# RAM.net
KiCad netlist of a schematic drawn in Altium Designer
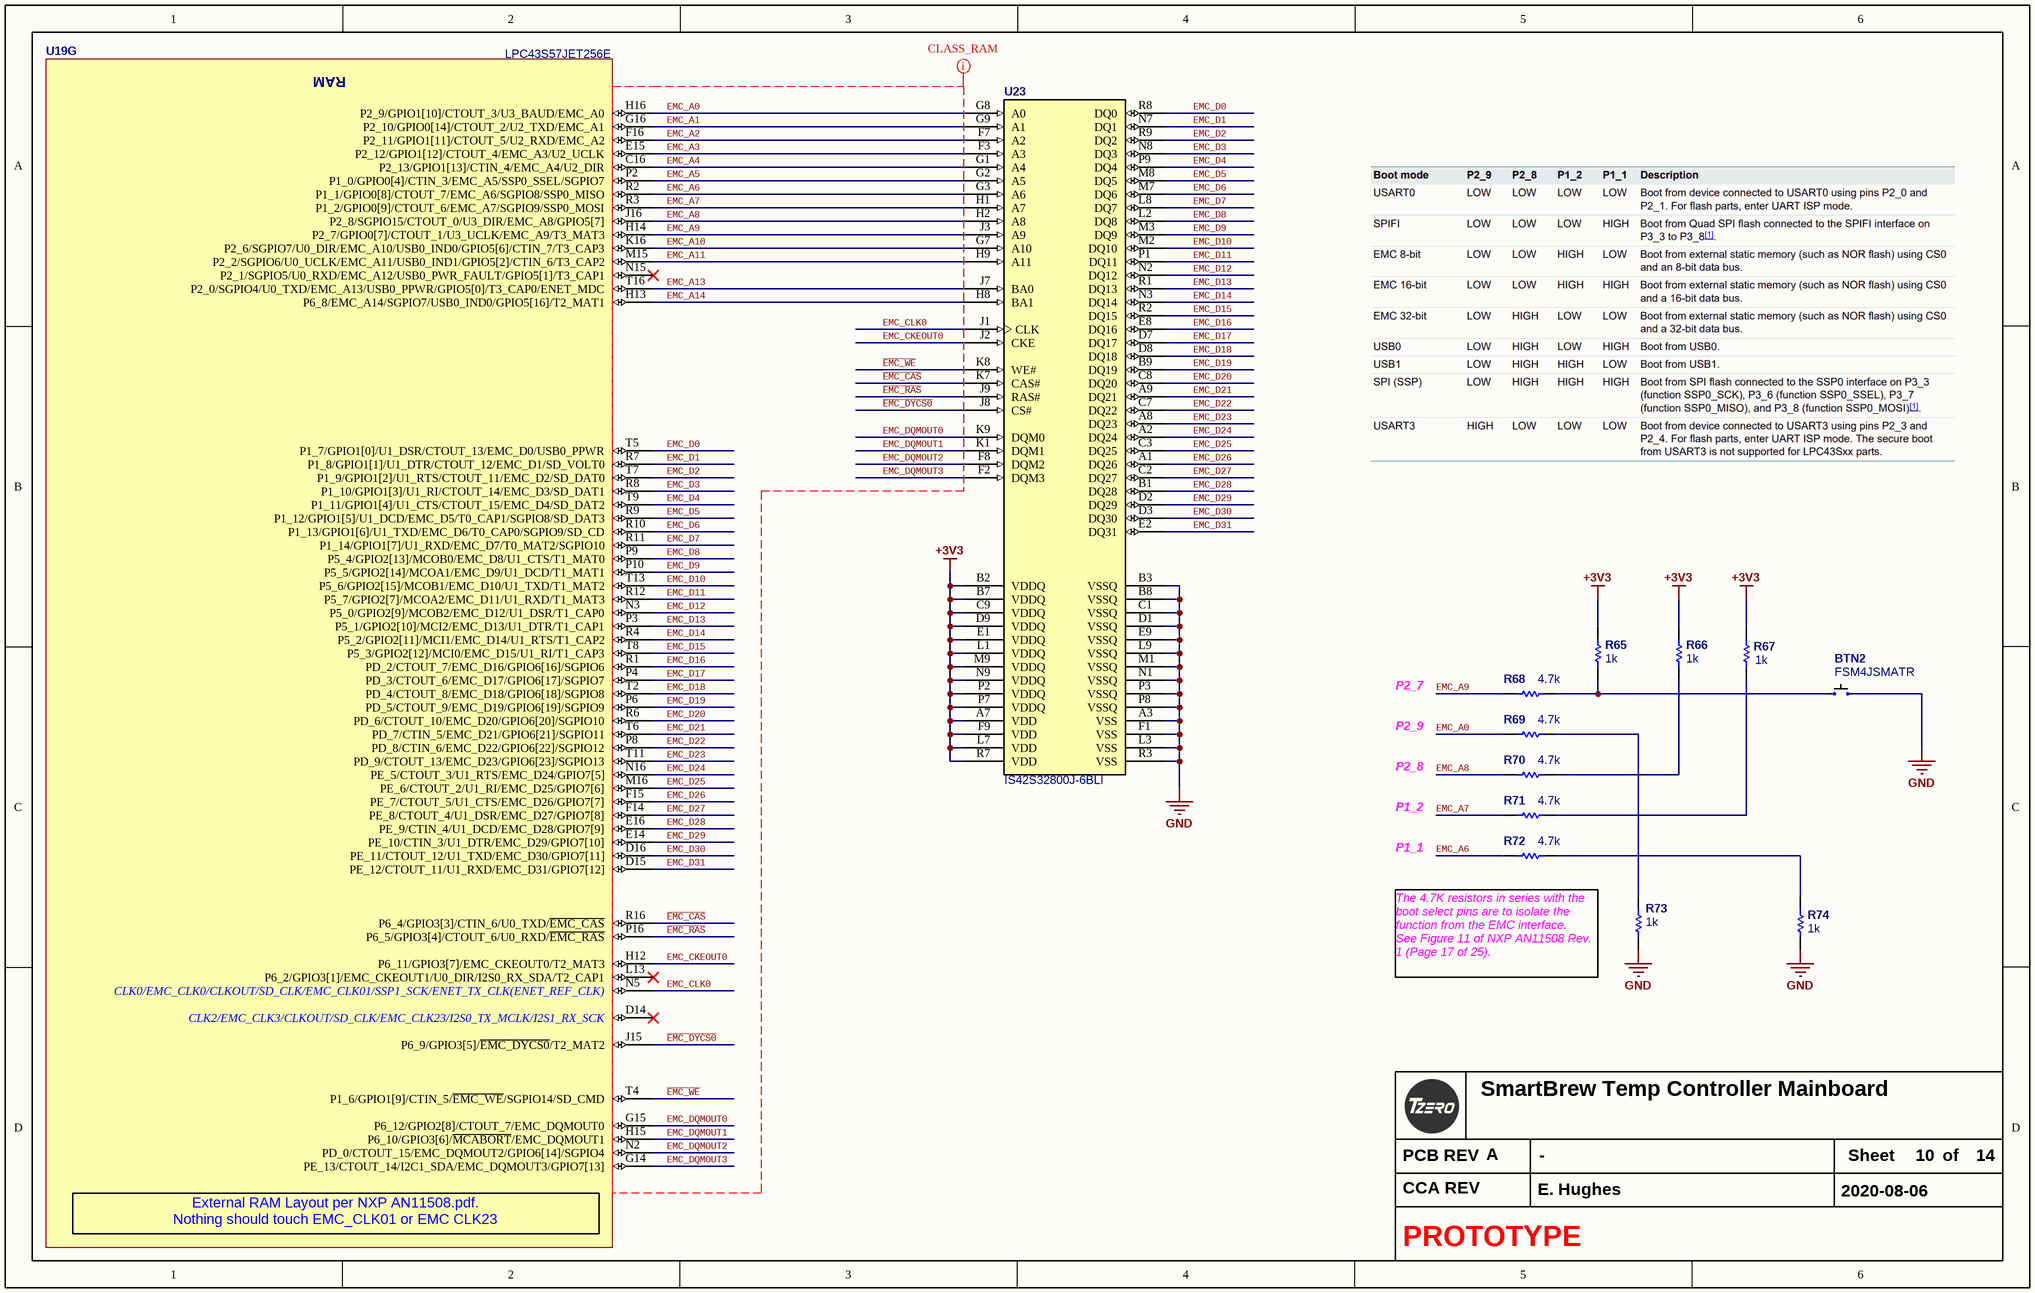
[diagram p0: RAM.SchDoc]

(export (version "E")
  (design (tool "Eeschema 10.0.6"))
  (components
    (comp (ref "BTN2")
      (value "FSM4JSMATR")
      (footprint "FSM4JSMA")
      (description "SWITCH TACTILE SPST-NO 0.05A 12V")
      (fields (field (name "MANUFACTURER") "TE Connectivity"))
      (libsource (lib "eElectroMechanical") (part "FSM4JSMATR"))
    )
    (comp (ref "R65")
      (value "1k")
      (footprint "R0603_0.55MM_MD")
      (description "RES 1K OHM 1/10W 1% 0603 SMD")
      (fields
        (field (name "MANUFACTURER") "Panasonic Electronic Components")
        (field (name "MANUFACTURER PART NUMBER") "ERJ-3EKF1001V")
      )
      (libsource (lib "Resistors - Panasonic - AEC-Q200") (part "R_2P"))
    )
    (comp (ref "R66")
      (value "1k")
      (footprint "R0603_0.55MM_MD")
      (description "RES 1K OHM 1/10W 1% 0603 SMD")
      (fields
        (field (name "MANUFACTURER") "Panasonic Electronic Components")
        (field (name "MANUFACTURER PART NUMBER") "ERJ-3EKF1001V")
      )
      (libsource (lib "Resistors - Panasonic - AEC-Q200") (part "R_2P"))
    )
    (comp (ref "R67")
      (value "1k")
      (footprint "R0603_0.55MM_MD")
      (description "RES 1K OHM 1/10W 1% 0603 SMD")
      (fields
        (field (name "MANUFACTURER") "Panasonic Electronic Components")
        (field (name "MANUFACTURER PART NUMBER") "ERJ-3EKF1001V")
      )
      (libsource (lib "Resistors - Panasonic - AEC-Q200") (part "R_2P"))
    )
    (comp (ref "R68")
      (value "4.7k")
      (footprint "R0603_0.55MM_MD")
      (description "RES 4.7K OHM 1/10W 1% 0603 SMD")
      (fields
        (field (name "MANUFACTURER") "Panasonic Electronic Components")
        (field (name "MANUFACTURER PART NUMBER") "ERJ-3EKF4701V")
      )
      (libsource (lib "Resistors - Panasonic - AEC-Q200") (part "R_2P"))
    )
    (comp (ref "R69")
      (value "4.7k")
      (footprint "R0603_0.55MM_MD")
      (description "RES 4.7K OHM 1/10W 1% 0603 SMD")
      (fields
        (field (name "MANUFACTURER") "Panasonic Electronic Components")
        (field (name "MANUFACTURER PART NUMBER") "ERJ-3EKF4701V")
      )
      (libsource (lib "Resistors - Panasonic - AEC-Q200") (part "R_2P"))
    )
    (comp (ref "R70")
      (value "4.7k")
      (footprint "R0603_0.55MM_MD")
      (description "RES 4.7K OHM 1/10W 1% 0603 SMD")
      (fields
        (field (name "MANUFACTURER") "Panasonic Electronic Components")
        (field (name "MANUFACTURER PART NUMBER") "ERJ-3EKF4701V")
      )
      (libsource (lib "Resistors - Panasonic - AEC-Q200") (part "R_2P"))
    )
    (comp (ref "R71")
      (value "4.7k")
      (footprint "R0603_0.55MM_MD")
      (description "RES 4.7K OHM 1/10W 1% 0603 SMD")
      (fields
        (field (name "MANUFACTURER") "Panasonic Electronic Components")
        (field (name "MANUFACTURER PART NUMBER") "ERJ-3EKF4701V")
      )
      (libsource (lib "Resistors - Panasonic - AEC-Q200") (part "R_2P"))
    )
    (comp (ref "R72")
      (value "4.7k")
      (footprint "R0603_0.55MM_MD")
      (description "RES 4.7K OHM 1/10W 1% 0603 SMD")
      (fields
        (field (name "MANUFACTURER") "Panasonic Electronic Components")
        (field (name "MANUFACTURER PART NUMBER") "ERJ-3EKF4701V")
      )
      (libsource (lib "Resistors - Panasonic - AEC-Q200") (part "R_2P"))
    )
    (comp (ref "R73")
      (value "1k")
      (footprint "R0603_0.55MM_MD")
      (description "RES 1K OHM 1/10W 1% 0603 SMD")
      (fields
        (field (name "MANUFACTURER") "Panasonic Electronic Components")
        (field (name "MANUFACTURER PART NUMBER") "ERJ-3EKF1001V")
      )
      (libsource (lib "Resistors - Panasonic - AEC-Q200") (part "R_2P"))
    )
    (comp (ref "R74")
      (value "1k")
      (footprint "R0603_0.55MM_MD")
      (description "RES 1K OHM 1/10W 1% 0603 SMD")
      (fields
        (field (name "MANUFACTURER") "Panasonic Electronic Components")
        (field (name "MANUFACTURER PART NUMBER") "ERJ-3EKF1001V")
      )
      (libsource (lib "Resistors - Panasonic - AEC-Q200") (part "R_2P"))
    )
    (comp (ref "U19")
      (value "LPC43S57JET256E")
      (footprint "Integrated Circuits BGA-N:LBGA256 16X16 1700X1700X155")
      (description "ARM Microcontrollers - MCU CortexM0/4 32bit 1MB Cortex-M4/M0")
      (fields (field (name "MANUFACTURER") "NXP Semiconductors"))
      (libsource (lib "eIC") (part "LPC43S57JET256E"))
    )
    (comp (ref "U23")
      (value "IS42S32800J-6BLI")
      (footprint "Integrated Circuits BGA-N:TFBGA90_8x13")
      (description "IC DRAM 256M PARALLEL 90TFBGA")
      (fields (field (name "MANUFACTURER") "ISSI"))
      (libsource (lib "Memory-N") (part "IS42S32800J-6BLI"))
    )
  )
  (nets
    (net (code "1") (name "+3V3") (class "Default")
      (node (ref "R65") (pin "2") (pinfunction "2_2") (pintype "passive"))
      (node (ref "R66") (pin "2") (pinfunction "2_2") (pintype "passive"))
      (node (ref "R67") (pin "2") (pinfunction "2_2") (pintype "passive"))
      (node (ref "U23") (pin "A7") (pinfunction "VDD_A7") (pintype "power_in"))
      (node (ref "U23") (pin "B2") (pinfunction "VDDQ_B2") (pintype "power_in"))
      (node (ref "U23") (pin "B7") (pinfunction "VDDQ_B7") (pintype "power_in"))
      (node (ref "U23") (pin "C9") (pinfunction "VDDQ_C9") (pintype "power_in"))
      (node (ref "U23") (pin "D9") (pinfunction "VDDQ_D9") (pintype "power_in"))
      (node (ref "U23") (pin "E1") (pinfunction "VDDQ_E1") (pintype "power_in"))
      (node (ref "U23") (pin "F9") (pinfunction "VDD_F9") (pintype "power_in"))
      (node (ref "U23") (pin "L1") (pinfunction "VDDQ_L1") (pintype "power_in"))
      (node (ref "U23") (pin "L7") (pinfunction "VDD_L7") (pintype "power_in"))
      (node (ref "U23") (pin "M9") (pinfunction "VDDQ_M9") (pintype "power_in"))
      (node (ref "U23") (pin "N9") (pinfunction "VDDQ_N9") (pintype "power_in"))
      (node (ref "U23") (pin "P2") (pinfunction "VDDQ_P2") (pintype "power_in"))
      (node (ref "U23") (pin "P7") (pinfunction "VDDQ_P7") (pintype "power_in"))
      (node (ref "U23") (pin "R7") (pinfunction "VDD_R7") (pintype "power_in"))
    )
    (net (code "2") (name "/EMC_A0") (class "Default")
      (node (ref "R69") (pin "2") (pinfunction "2_2") (pintype "passive"))
      (node (ref "U19") (pin "H16") (pinfunction "P2_9/GPIO1[10]/CTOUT_3/U3_BAUD/EMC_A0_H16") (pintype "bidirectional"))
      (node (ref "U23") (pin "G8") (pinfunction "A0_G8") (pintype "input"))
    )
    (net (code "3") (name "/EMC_A1") (class "Default")
      (node (ref "U19") (pin "G16") (pinfunction "P2_10/GPIO0[14]/CTOUT_2/U2_TXD/EMC_A1_G16") (pintype "bidirectional"))
      (node (ref "U23") (pin "G9") (pinfunction "A1_G9") (pintype "input"))
    )
    (net (code "4") (name "/EMC_A2") (class "Default")
      (node (ref "U19") (pin "F16") (pinfunction "P2_11/GPIO1[11]/CTOUT_5/U2_RXD/EMC_A2_F16") (pintype "bidirectional"))
      (node (ref "U23") (pin "F7") (pinfunction "A2_F7") (pintype "input"))
    )
    (net (code "5") (name "/EMC_A3") (class "Default")
      (node (ref "U19") (pin "E15") (pinfunction "P2_12/GPIO1[12]/CTOUT_4/EMC_A3/U2_UCLK_E15") (pintype "bidirectional"))
      (node (ref "U23") (pin "F3") (pinfunction "A3_F3") (pintype "input"))
    )
    (net (code "6") (name "/EMC_A4") (class "Default")
      (node (ref "U19") (pin "C16") (pinfunction "P2_13/GPIO1[13]/CTIN_4/EMC_A4/U2_DIR_C16") (pintype "bidirectional"))
      (node (ref "U23") (pin "G1") (pinfunction "A4_G1") (pintype "input"))
    )
    (net (code "7") (name "/EMC_A5") (class "Default")
      (node (ref "U19") (pin "P2") (pinfunction "P1_0/GPIO0[4]/CTIN_3/EMC_A5/SSP0_SSEL/SGPIO7_P2") (pintype "bidirectional"))
      (node (ref "U23") (pin "G2") (pinfunction "A5_G2") (pintype "input"))
    )
    (net (code "8") (name "/EMC_A6") (class "Default")
      (node (ref "R72") (pin "2") (pinfunction "2_2") (pintype "passive"))
      (node (ref "U19") (pin "R2") (pinfunction "P1_1/GPIO0[8]/CTOUT_7/EMC_A6/SGPIO8/SSP0_MISO_R2") (pintype "bidirectional"))
      (node (ref "U23") (pin "G3") (pinfunction "A6_G3") (pintype "input"))
    )
    (net (code "9") (name "/EMC_A7") (class "Default")
      (node (ref "R71") (pin "2") (pinfunction "2_2") (pintype "passive"))
      (node (ref "U19") (pin "R3") (pinfunction "P1_2/GPIO0[9]/CTOUT_6/EMC_A7/SGPIO9/SSP0_MOSI_R3") (pintype "bidirectional"))
      (node (ref "U23") (pin "H1") (pinfunction "A7_H1") (pintype "input"))
    )
    (net (code "10") (name "/EMC_A8") (class "Default")
      (node (ref "R70") (pin "2") (pinfunction "2_2") (pintype "passive"))
      (node (ref "U19") (pin "J16") (pinfunction "P2_8/SGPIO15/CTOUT_0/U3_DIR/EMC_A8/GPIO5[7]_J16") (pintype "bidirectional"))
      (node (ref "U23") (pin "H2") (pinfunction "A8_H2") (pintype "input"))
    )
    (net (code "11") (name "/EMC_A9") (class "Default")
      (node (ref "R68") (pin "2") (pinfunction "2_2") (pintype "passive"))
      (node (ref "U19") (pin "H14") (pinfunction "P2_7/GPIO0[7]/CTOUT_1/U3_UCLK/EMC_A9/T3_MAT3_H14") (pintype "bidirectional"))
      (node (ref "U23") (pin "J3") (pinfunction "A9_J3") (pintype "input"))
    )
    (net (code "12") (name "/EMC_A10") (class "Default")
      (node (ref "U19") (pin "K16") (pinfunction "P2_6/SGPIO7/U0_DIR/EMC_A10/USB0_IND0/GPIO5[6]/CTIN_7/T3_CAP3_K16") (pintype "bidirectional"))
      (node (ref "U23") (pin "G7") (pinfunction "A10_G7") (pintype "input"))
    )
    (net (code "13") (name "/EMC_A11") (class "Default")
      (node (ref "U19") (pin "M15") (pinfunction "P2_2/SGPIO6/U0_UCLK/EMC_A11/USB0_IND1/GPIO5[2]/CTIN_6/T3_CAP2_M15") (pintype "bidirectional"))
      (node (ref "U23") (pin "H9") (pinfunction "A11_H9") (pintype "input"))
    )
    (net (code "14") (name "/EMC_A13") (class "Default")
      (node (ref "U19") (pin "T16") (pinfunction "P2_0/SGPIO4/U0_TXD/EMC_A13/USB0_PPWR/GPIO5[0]/T3_CAP0/ENET_MDC_T16") (pintype "bidirectional"))
      (node (ref "U23") (pin "J7") (pinfunction "BA0_J7") (pintype "input"))
    )
    (net (code "15") (name "/EMC_A14") (class "Default")
      (node (ref "U19") (pin "H13") (pinfunction "P6_8/EMC_A14/SGPIO7/USB0_IND0/GPIO5[16]/T2_MAT1_H13") (pintype "bidirectional"))
      (node (ref "U23") (pin "H8") (pinfunction "BA1_H8") (pintype "input"))
    )
    (net (code "16") (name "/EMC_CAS") (class "Default")
      (node (ref "U19") (pin "R16") (pinfunction "P6_4/GPIO3[3]/CTIN_6/U0_TXD/~{EMC_CAS}_R16") (pintype "bidirectional"))
      (node (ref "U23") (pin "K7") (pinfunction "CAS#_K7") (pintype "input"))
    )
    (net (code "17") (name "/EMC_CKEOUT0") (class "Default")
      (node (ref "U19") (pin "H12") (pinfunction "P6_11/GPIO3[7]/EMC_CKEOUT0/T2_MAT3_H12") (pintype "bidirectional"))
      (node (ref "U23") (pin "J2") (pinfunction "CKE_J2") (pintype "input"))
    )
    (net (code "18") (name "/EMC_CLK0") (class "Default")
      (node (ref "U19") (pin "N5") (pinfunction "CLK0/EMC_CLK0/CLKOUT/SD_CLK/EMC_CLK01/SSP1_SCK/ENET_TX_CLK(ENET_REF_CLK)_N5") (pintype "bidirectional"))
      (node (ref "U23") (pin "J1") (pinfunction "CLK_J1") (pintype "input"))
    )
    (net (code "19") (name "/EMC_D0") (class "Default")
      (node (ref "U19") (pin "T5") (pinfunction "P1_7/GPIO1[0]/U1_DSR/CTOUT_13/EMC_D0/USB0_PPWR_T5") (pintype "bidirectional"))
      (node (ref "U23") (pin "R8") (pinfunction "DQ0_R8") (pintype "bidirectional"))
    )
    (net (code "20") (name "/EMC_D1") (class "Default")
      (node (ref "U19") (pin "R7") (pinfunction "P1_8/GPIO1[1]/U1_DTR/CTOUT_12/EMC_D1/SD_VOLT0_R7") (pintype "bidirectional"))
      (node (ref "U23") (pin "N7") (pinfunction "DQ1_N7") (pintype "bidirectional"))
    )
    (net (code "21") (name "/EMC_D2") (class "Default")
      (node (ref "U19") (pin "T7") (pinfunction "P1_9/GPIO1[2]/U1_RTS/CTOUT_11/EMC_D2/SD_DAT0_T7") (pintype "bidirectional"))
      (node (ref "U23") (pin "R9") (pinfunction "DQ2_R9") (pintype "bidirectional"))
    )
    (net (code "22") (name "/EMC_D3") (class "Default")
      (node (ref "U19") (pin "R8") (pinfunction "P1_10/GPIO1[3]/U1_RI/CTOUT_14/EMC_D3/SD_DAT1_R8") (pintype "bidirectional"))
      (node (ref "U23") (pin "N8") (pinfunction "DQ3_N8") (pintype "bidirectional"))
    )
    (net (code "23") (name "/EMC_D4") (class "Default")
      (node (ref "U19") (pin "T9") (pinfunction "P1_11/GPIO1[4]/U1_CTS/CTOUT_15/EMC_D4/SD_DAT2_T9") (pintype "bidirectional"))
      (node (ref "U23") (pin "P9") (pinfunction "DQ4_P9") (pintype "bidirectional"))
    )
    (net (code "24") (name "/EMC_D5") (class "Default")
      (node (ref "U19") (pin "R9") (pinfunction "P1_12/GPIO1[5]/U1_DCD/EMC_D5/T0_CAP1/SGPIO8/SD_DAT3_R9") (pintype "bidirectional"))
      (node (ref "U23") (pin "M8") (pinfunction "DQ5_M8") (pintype "bidirectional"))
    )
    (net (code "25") (name "/EMC_D6") (class "Default")
      (node (ref "U19") (pin "R10") (pinfunction "P1_13/GPIO1[6]/U1_TXD/EMC_D6/T0_CAP0/SGPIO9/SD_CD_R10") (pintype "bidirectional"))
      (node (ref "U23") (pin "M7") (pinfunction "DQ6_M7") (pintype "bidirectional"))
    )
    (net (code "26") (name "/EMC_D7") (class "Default")
      (node (ref "U19") (pin "R11") (pinfunction "P1_14/GPIO1[7]/U1_RXD/EMC_D7/T0_MAT2/SGPIO10_R11") (pintype "bidirectional"))
      (node (ref "U23") (pin "L8") (pinfunction "DQ7_L8") (pintype "bidirectional"))
    )
    (net (code "27") (name "/EMC_D8") (class "Default")
      (node (ref "U19") (pin "P9") (pinfunction "P5_4/GPIO2[13]/MCOB0/EMC_D8/U1_CTS/T1_MAT0_P9") (pintype "bidirectional"))
      (node (ref "U23") (pin "L2") (pinfunction "DQ8_L2") (pintype "bidirectional"))
    )
    (net (code "28") (name "/EMC_D9") (class "Default")
      (node (ref "U19") (pin "P10") (pinfunction "P5_5/GPIO2[14]/MCOA1/EMC_D9/U1_DCD/T1_MAT1_P10") (pintype "bidirectional"))
      (node (ref "U23") (pin "M3") (pinfunction "DQ9_M3") (pintype "bidirectional"))
    )
    (net (code "29") (name "/EMC_D10") (class "Default")
      (node (ref "U19") (pin "T13") (pinfunction "P5_6/GPIO2[15]/MCOB1/EMC_D10/U1_TXD/T1_MAT2_T13") (pintype "bidirectional"))
      (node (ref "U23") (pin "M2") (pinfunction "DQ10_M2") (pintype "bidirectional"))
    )
    (net (code "30") (name "/EMC_D11") (class "Default")
      (node (ref "U19") (pin "R12") (pinfunction "P5_7/GPIO2[7]/MCOA2/EMC_D11/U1_RXD/T1_MAT3_R12") (pintype "bidirectional"))
      (node (ref "U23") (pin "P1") (pinfunction "DQ11_P1") (pintype "bidirectional"))
    )
    (net (code "31") (name "/EMC_D12") (class "Default")
      (node (ref "U19") (pin "N3") (pinfunction "P5_0/GPIO2[9]/MCOB2/EMC_D12/U1_DSR/T1_CAP0_N3") (pintype "bidirectional"))
      (node (ref "U23") (pin "N2") (pinfunction "DQ12_N2") (pintype "bidirectional"))
    )
    (net (code "32") (name "/EMC_D13") (class "Default")
      (node (ref "U19") (pin "P3") (pinfunction "P5_1/GPIO2[10]/MCI2/EMC_D13/U1_DTR/T1_CAP1_P3") (pintype "bidirectional"))
      (node (ref "U23") (pin "R1") (pinfunction "DQ13_R1") (pintype "bidirectional"))
    )
    (net (code "33") (name "/EMC_D14") (class "Default")
      (node (ref "U19") (pin "R4") (pinfunction "P5_2/GPIO2[11]/MCI1/EMC_D14/U1_RTS/T1_CAP2_R4") (pintype "bidirectional"))
      (node (ref "U23") (pin "N3") (pinfunction "DQ14_N3") (pintype "bidirectional"))
    )
    (net (code "34") (name "/EMC_D15") (class "Default")
      (node (ref "U19") (pin "T8") (pinfunction "P5_3/GPIO2[12]/MCI0/EMC_D15/U1_RI/T1_CAP3_T8") (pintype "bidirectional"))
      (node (ref "U23") (pin "R2") (pinfunction "DQ15_R2") (pintype "bidirectional"))
    )
    (net (code "35") (name "/EMC_D16") (class "Default")
      (node (ref "U19") (pin "R1") (pinfunction "PD_2/CTOUT_7/EMC_D16/GPIO6[16]/SGPIO6_R1") (pintype "bidirectional"))
      (node (ref "U23") (pin "E8") (pinfunction "DQ16_E8") (pintype "bidirectional"))
    )
    (net (code "36") (name "/EMC_D17") (class "Default")
      (node (ref "U19") (pin "P4") (pinfunction "PD_3/CTOUT_6/EMC_D17/GPIO6[17]/SGPIO7_P4") (pintype "bidirectional"))
      (node (ref "U23") (pin "D7") (pinfunction "DQ17_D7") (pintype "bidirectional"))
    )
    (net (code "37") (name "/EMC_D18") (class "Default")
      (node (ref "U19") (pin "T2") (pinfunction "PD_4/CTOUT_8/EMC_D18/GPIO6[18]/SGPIO8_T2") (pintype "bidirectional"))
      (node (ref "U23") (pin "D8") (pinfunction "DQ18_D8") (pintype "bidirectional"))
    )
    (net (code "38") (name "/EMC_D19") (class "Default")
      (node (ref "U19") (pin "P6") (pinfunction "PD_5/CTOUT_9/EMC_D19/GPIO6[19]/SGPIO9_P6") (pintype "bidirectional"))
      (node (ref "U23") (pin "B9") (pinfunction "DQ19_B9") (pintype "bidirectional"))
    )
    (net (code "39") (name "/EMC_D20") (class "Default")
      (node (ref "U19") (pin "R6") (pinfunction "PD_6/CTOUT_10/EMC_D20/GPIO6[20]/SGPIO10_R6") (pintype "bidirectional"))
      (node (ref "U23") (pin "C8") (pinfunction "DQ20_C8") (pintype "bidirectional"))
    )
    (net (code "40") (name "/EMC_D21") (class "Default")
      (node (ref "U19") (pin "T6") (pinfunction "PD_7/CTIN_5/EMC_D21/GPIO6[21]/SGPIO11_T6") (pintype "bidirectional"))
      (node (ref "U23") (pin "A9") (pinfunction "DQ21_A9") (pintype "bidirectional"))
    )
    (net (code "41") (name "/EMC_D22") (class "Default")
      (node (ref "U19") (pin "P8") (pinfunction "PD_8/CTIN_6/EMC_D22/GPIO6[22]/SGPIO12_P8") (pintype "bidirectional"))
      (node (ref "U23") (pin "C7") (pinfunction "DQ22_C7") (pintype "bidirectional"))
    )
    (net (code "42") (name "/EMC_D23") (class "Default")
      (node (ref "U19") (pin "T11") (pinfunction "PD_9/CTOUT_13/EMC_D23/GPIO6[23]/SGPIO13_T11") (pintype "bidirectional"))
      (node (ref "U23") (pin "A8") (pinfunction "DQ23_A8") (pintype "bidirectional"))
    )
    (net (code "43") (name "/EMC_D24") (class "Default")
      (node (ref "U19") (pin "N16") (pinfunction "PE_5/CTOUT_3/U1_RTS/EMC_D24/GPIO7[5]_N16") (pintype "bidirectional"))
      (node (ref "U23") (pin "A2") (pinfunction "DQ24_A2") (pintype "bidirectional"))
    )
    (net (code "44") (name "/EMC_D25") (class "Default")
      (node (ref "U19") (pin "M16") (pinfunction "PE_6/CTOUT_2/U1_RI/EMC_D25/GPIO7[6]_M16") (pintype "bidirectional"))
      (node (ref "U23") (pin "C3") (pinfunction "DQ25_C3") (pintype "bidirectional"))
    )
    (net (code "45") (name "/EMC_D26") (class "Default")
      (node (ref "U19") (pin "F15") (pinfunction "PE_7/CTOUT_5/U1_CTS/EMC_D26/GPIO7[7]_F15") (pintype "bidirectional"))
      (node (ref "U23") (pin "A1") (pinfunction "DQ26_A1") (pintype "bidirectional"))
    )
    (net (code "46") (name "/EMC_D27") (class "Default")
      (node (ref "U19") (pin "F14") (pinfunction "PE_8/CTOUT_4/U1_DSR/EMC_D27/GPIO7[8]_F14") (pintype "bidirectional"))
      (node (ref "U23") (pin "C2") (pinfunction "DQ27_C2") (pintype "bidirectional"))
    )
    (net (code "47") (name "/EMC_D28") (class "Default")
      (node (ref "U19") (pin "E16") (pinfunction "PE_9/CTIN_4/U1_DCD/EMC_D28/GPIO7[9]_E16") (pintype "bidirectional"))
      (node (ref "U23") (pin "B1") (pinfunction "DQ28_B1") (pintype "bidirectional"))
    )
    (net (code "48") (name "/EMC_D29") (class "Default")
      (node (ref "U19") (pin "E14") (pinfunction "PE_10/CTIN_3/U1_DTR/EMC_D29/GPIO7[10]_E14") (pintype "bidirectional"))
      (node (ref "U23") (pin "D2") (pinfunction "DQ29_D2") (pintype "bidirectional"))
    )
    (net (code "49") (name "/EMC_D30") (class "Default")
      (node (ref "U19") (pin "D16") (pinfunction "PE_11/CTOUT_12/U1_TXD/EMC_D30/GPIO7[11]_D16") (pintype "bidirectional"))
      (node (ref "U23") (pin "D3") (pinfunction "DQ30_D3") (pintype "bidirectional"))
    )
    (net (code "50") (name "/EMC_D31") (class "Default")
      (node (ref "U19") (pin "D15") (pinfunction "PE_12/CTOUT_11/U1_RXD/EMC_D31/GPIO7[12]_D15") (pintype "bidirectional"))
      (node (ref "U23") (pin "E2") (pinfunction "DQ31_E2") (pintype "bidirectional"))
    )
    (net (code "51") (name "/EMC_DQMOUT0") (class "Default")
      (node (ref "U19") (pin "G15") (pinfunction "P6_12/GPIO2[8]/CTOUT_7/EMC_DQMOUT0_G15") (pintype "bidirectional"))
      (node (ref "U23") (pin "K9") (pinfunction "DQM0_K9") (pintype "input"))
    )
    (net (code "52") (name "/EMC_DQMOUT1") (class "Default")
      (node (ref "U19") (pin "H15") (pinfunction "P6_10/GPIO3[6]/~{MCABORT}/EMC_DQMOUT1_H15") (pintype "bidirectional"))
      (node (ref "U23") (pin "K1") (pinfunction "DQM1_K1") (pintype "input"))
    )
    (net (code "53") (name "/EMC_DQMOUT2") (class "Default")
      (node (ref "U19") (pin "N2") (pinfunction "PD_0/CTOUT_15/EMC_DQMOUT2/GPIO6[14]/SGPIO4_N2") (pintype "bidirectional"))
      (node (ref "U23") (pin "F8") (pinfunction "DQM2_F8") (pintype "input"))
    )
    (net (code "54") (name "/EMC_DQMOUT3") (class "Default")
      (node (ref "U19") (pin "G14") (pinfunction "PE_13/CTOUT_14/I2C1_SDA/EMC_DQMOUT3/GPIO7[13]_G14") (pintype "bidirectional"))
      (node (ref "U23") (pin "F2") (pinfunction "DQM3_F2") (pintype "input"))
    )
    (net (code "55") (name "/EMC_DYCS0") (class "Default")
      (node (ref "U19") (pin "J15") (pinfunction "P6_9/GPIO3[5]/~{EMC_DYCS0}/T2_MAT2_J15") (pintype "bidirectional"))
      (node (ref "U23") (pin "J8") (pinfunction "CS#_J8") (pintype "input"))
    )
    (net (code "56") (name "/EMC_RAS") (class "Default")
      (node (ref "U19") (pin "P16") (pinfunction "P6_5/GPIO3[4]/CTOUT_6/U0_RXD/~{EMC_RAS}_P16") (pintype "bidirectional"))
      (node (ref "U23") (pin "J9") (pinfunction "RAS#_J9") (pintype "input"))
    )
    (net (code "57") (name "/EMC_WE") (class "Default")
      (node (ref "U19") (pin "T4") (pinfunction "P1_6/GPIO1[9]/CTIN_5/~{EMC_WE}/SGPIO14/SD_CMD_T4") (pintype "bidirectional"))
      (node (ref "U23") (pin "K8") (pinfunction "WE#_K8") (pintype "input"))
    )
    (net (code "58") (name "GND") (class "Default")
      (node (ref "BTN2") (pin "B") (pinfunction "B_B") (pintype "passive"))
      (node (ref "R73") (pin "1") (pinfunction "1_1") (pintype "passive"))
      (node (ref "R74") (pin "1") (pinfunction "1_1") (pintype "passive"))
      (node (ref "U23") (pin "A3") (pinfunction "VSS_A3") (pintype "power_in"))
      (node (ref "U23") (pin "B3") (pinfunction "VSSQ_B3") (pintype "power_in"))
      (node (ref "U23") (pin "B8") (pinfunction "VSSQ_B8") (pintype "power_in"))
      (node (ref "U23") (pin "C1") (pinfunction "VSSQ_C1") (pintype "power_in"))
      (node (ref "U23") (pin "D1") (pinfunction "VSSQ_D1") (pintype "power_in"))
      (node (ref "U23") (pin "E9") (pinfunction "VSSQ_E9") (pintype "power_in"))
      (node (ref "U23") (pin "F1") (pinfunction "VSS_F1") (pintype "power_in"))
      (node (ref "U23") (pin "L3") (pinfunction "VSS_L3") (pintype "power_in"))
      (node (ref "U23") (pin "L9") (pinfunction "VSSQ_L9") (pintype "power_in"))
      (node (ref "U23") (pin "M1") (pinfunction "VSSQ_M1") (pintype "power_in"))
      (node (ref "U23") (pin "N1") (pinfunction "VSSQ_N1") (pintype "power_in"))
      (node (ref "U23") (pin "P3") (pinfunction "VSSQ_P3") (pintype "power_in"))
      (node (ref "U23") (pin "P8") (pinfunction "VSSQ_P8") (pintype "power_in"))
      (node (ref "U23") (pin "R3") (pinfunction "VSS_R3") (pintype "power_in"))
    )
    (net (code "59") (name "Net-(BTN2-PadA)") (class "Default")
      (node (ref "BTN2") (pin "A") (pinfunction "A_A") (pintype "passive"))
      (node (ref "R65") (pin "1") (pinfunction "1_1") (pintype "passive"))
      (node (ref "R68") (pin "1") (pinfunction "1_1") (pintype "passive"))
    )
    (net (code "60") (name "Net-(R66-Pad1)") (class "Default")
      (node (ref "R66") (pin "1") (pinfunction "1_1") (pintype "passive"))
      (node (ref "R70") (pin "1") (pinfunction "1_1") (pintype "passive"))
    )
    (net (code "61") (name "Net-(R67-Pad1)") (class "Default")
      (node (ref "R67") (pin "1") (pinfunction "1_1") (pintype "passive"))
      (node (ref "R71") (pin "1") (pinfunction "1_1") (pintype "passive"))
    )
    (net (code "62") (name "Net-(R69-Pad1)") (class "Default")
      (node (ref "R69") (pin "1") (pinfunction "1_1") (pintype "passive"))
      (node (ref "R73") (pin "2") (pinfunction "2_2") (pintype "passive"))
    )
    (net (code "63") (name "Net-(R72-Pad1)") (class "Default")
      (node (ref "R72") (pin "1") (pinfunction "1_1") (pintype "passive"))
      (node (ref "R74") (pin "2") (pinfunction "2_2") (pintype "passive"))
    )
    (net (code "64") (name "unconnected-(U19G-CLK2{slash}EMC_CLK3{slash}CLKOUT{slash}SD_CLK{slash}EMC_CLK23{slash}I2S0_TX_MCLK{slash}I2S1_RX_SCK-PadD14)") (class "Default")
      (node (ref "U19") (pin "D14") (pinfunction "CLK2/EMC_CLK3/CLKOUT/SD_CLK/EMC_CLK23/I2S0_TX_MCLK/I2S1_RX_SCK_D14") (pintype "bidirectional+no_connect"))
    )
    (net (code "65") (name "unconnected-(U19G-P2_1{slash}SGPIO5{slash}U0_RXD{slash}EMC_A12{slash}USB0_PWR_FAULT{slash}GPIO5[1]{slash}T3_CAP1-PadN15)") (class "Default")
      (node (ref "U19") (pin "N15") (pinfunction "P2_1/SGPIO5/U0_RXD/EMC_A12/USB0_PWR_FAULT/GPIO5[1]/T3_CAP1_N15") (pintype "bidirectional+no_connect"))
    )
    (net (code "66") (name "unconnected-(U19G-P6_2{slash}GPIO3[1]{slash}EMC_CKEOUT1{slash}U0_DIR{slash}I2S0_RX_SDA{slash}T2_CAP1-PadL13)") (class "Default")
      (node (ref "U19") (pin "L13") (pinfunction "P6_2/GPIO3[1]/EMC_CKEOUT1/U0_DIR/I2S0_RX_SDA/T2_CAP1_L13") (pintype "bidirectional+no_connect"))
    )
  )
)
